# Power_Supply.net
KiCad netlist of a schematic drawn in Altium Designer
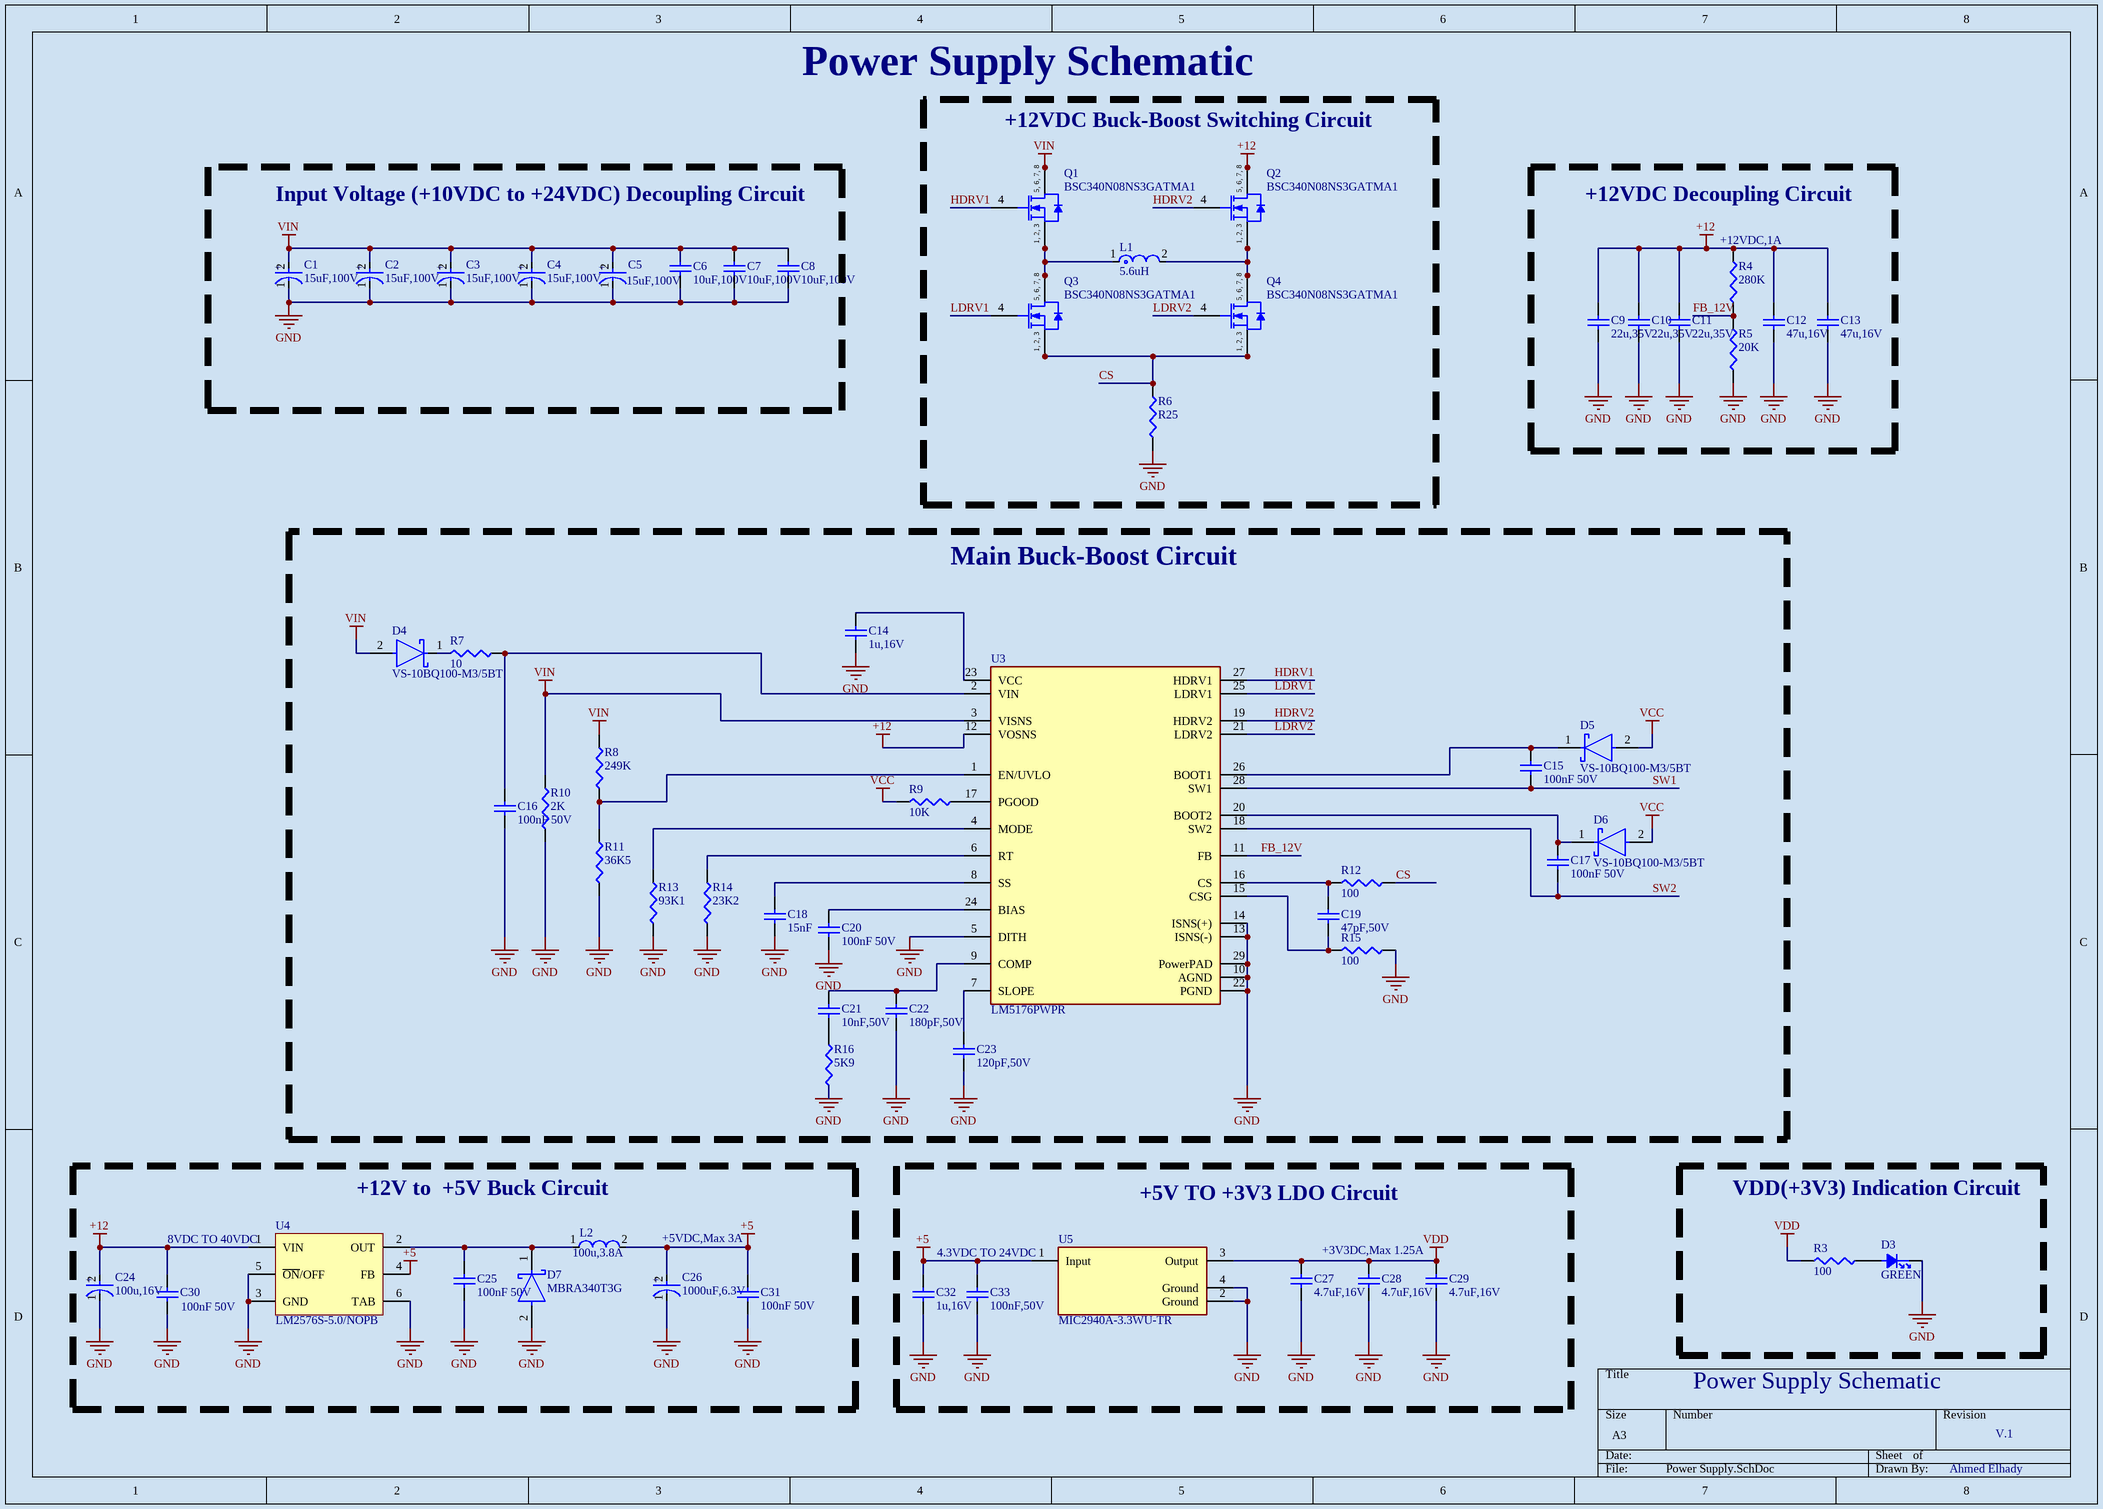
[diagram p0: Power Supply.SchDoc]

(export (version "E")
  (design (tool "Eeschema 10.0.6"))
  (components
    (comp (ref "C1")
      (value "15uF,100V")
      (footprint "FP-SMT-CAP-15U-100V-ELECTROLTIC")
      (description "15 µF 100 V Aluminum - Polymer Capacitors Radial, Can - SMD 40mOhm 1000 Hrs @ 125°C")
      (fields (field (name "MANUFACTURER") "Panasonic") (field (name "MANUFACTURER PART NUMBER") "100SXV15M"))
      (libsource (lib "Sch for NFC") (part "100SXV15M"))
    )
    (comp (ref "C2")
      (value "15uF,100V")
      (footprint "FP-SMT-CAP-15U-100V-ELECTROLTIC")
      (description "15 µF 100 V Aluminum - Polymer Capacitors Radial, Can - SMD 40mOhm 1000 Hrs @ 125°C")
      (fields (field (name "MANUFACTURER") "Panasonic") (field (name "MANUFACTURER PART NUMBER") "100SXV15M"))
      (libsource (lib "Sch for NFC") (part "100SXV15M"))
    )
    (comp (ref "C3")
      (value "15uF,100V")
      (footprint "FP-SMT-CAP-15U-100V-ELECTROLTIC")
      (description "15 µF 100 V Aluminum - Polymer Capacitors Radial, Can - SMD 40mOhm 1000 Hrs @ 125°C")
      (fields (field (name "MANUFACTURER") "Panasonic") (field (name "MANUFACTURER PART NUMBER") "100SXV15M"))
      (libsource (lib "Sch for NFC") (part "100SXV15M"))
    )
    (comp (ref "C4")
      (value "15uF,100V")
      (footprint "FP-SMT-CAP-15U-100V-ELECTROLTIC")
      (description "15 µF 100 V Aluminum - Polymer Capacitors Radial, Can - SMD 40mOhm 1000 Hrs @ 125°C")
      (fields (field (name "MANUFACTURER") "Panasonic") (field (name "MANUFACTURER PART NUMBER") "100SXV15M"))
      (libsource (lib "Sch for NFC") (part "100SXV15M"))
    )
    (comp (ref "C5")
      (value "15uF,100V")
      (footprint "FP-SMT-CAP-15U-100V-ELECTROLTIC")
      (description "15 µF 100 V Aluminum - Polymer Capacitors Radial, Can - SMD 40mOhm 1000 Hrs @ 125°C")
      (fields (field (name "MANUFACTURER") "Panasonic") (field (name "MANUFACTURER PART NUMBER") "100SXV15M"))
      (libsource (lib "Sch for NFC") (part "100SXV15M"))
    )
    (comp (ref "C6")
      (value "10uF,100V")
      (footprint "CAP-1210-10U-100V")
      (description "10 µF ±10% 100V Ceramic Capacitor X7R 1210 (3225 Metric)")
      (fields
        (field (name "MANUFACTURER") "TDK")
        (field (name "MANUFACTURER PART NUMBER") "C3225X7R2A106K250AC")
      )
      (libsource (lib "Sch for NFC") (part "C3225X7R2A106K250AC"))
    )
    (comp (ref "C7")
      (value "10uF,100V")
      (footprint "CAP-1210-10U-100V")
      (description "10 µF ±10% 100V Ceramic Capacitor X7R 1210 (3225 Metric)")
      (fields
        (field (name "MANUFACTURER") "TDK")
        (field (name "MANUFACTURER PART NUMBER") "C3225X7R2A106K250AC")
      )
      (libsource (lib "Sch for NFC") (part "C3225X7R2A106K250AC"))
    )
    (comp (ref "C8")
      (value "10uF,100V")
      (footprint "CAP-1210-10U-100V")
      (description "10 µF ±10% 100V Ceramic Capacitor X7R 1210 (3225 Metric)")
      (fields
        (field (name "MANUFACTURER") "TDK")
        (field (name "MANUFACTURER PART NUMBER") "C3225X7R2A106K250AC")
      )
      (libsource (lib "Sch for NFC") (part "C3225X7R2A106K250AC"))
    )
    (comp (ref "C9")
      (value "22u,35V")
      (footprint "TDK_0805-22uF-35V")
      (description "22 µF ±20% 35V Ceramic Capacitor X5R 0805 (2012 Metric)")
      (fields
        (field (name "MANUFACTURER") "TDK")
        (field (name "MANUFACTURER PART NUMBER") "C2012X5R1V226M125AC")
      )
      (libsource (lib "Sch for NFC") (part "C2012X5R1V226M125AC"))
    )
    (comp (ref "C10")
      (value "22u,35V")
      (footprint "TDK_0805-22uF-35V")
      (description "22 µF ±20% 35V Ceramic Capacitor X5R 0805 (2012 Metric)")
      (fields
        (field (name "MANUFACTURER") "TDK")
        (field (name "MANUFACTURER PART NUMBER") "C2012X5R1V226M125AC")
      )
      (libsource (lib "Sch for NFC") (part "C2012X5R1V226M125AC"))
    )
    (comp (ref "C11")
      (value "22u,35V")
      (footprint "TDK_0805-22uF-35V")
      (description "22 µF ±20% 35V Ceramic Capacitor X5R 0805 (2012 Metric)")
      (fields
        (field (name "MANUFACTURER") "TDK")
        (field (name "MANUFACTURER PART NUMBER") "C2012X5R1V226M125AC")
      )
      (libsource (lib "Sch for NFC") (part "C2012X5R1V226M125AC"))
    )
    (comp (ref "C12")
      (value "47u,16V")
      (footprint "cap1210-47u-16v")
      (description "47 µF ±10% 16V Ceramic Capacitor X5R 1210 (3225 Metric)")
      (fields
        (field (name "MANUFACTURER") "Murata")
        (field (name "MANUFACTURER PART NUMBER") "GRM32ER61C476KE15L")
      )
      (libsource (lib "Sch for NFC") (part "GRM32ER61C476KE15L"))
    )
    (comp (ref "C13")
      (value "47u,16V")
      (footprint "cap1210-47u-16v")
      (description "47 µF ±10% 16V Ceramic Capacitor X5R 1210 (3225 Metric)")
      (fields
        (field (name "MANUFACTURER") "Murata")
        (field (name "MANUFACTURER PART NUMBER") "GRM32ER61C476KE15L")
      )
      (libsource (lib "Sch for NFC") (part "GRM32ER61C476KE15L"))
    )
    (comp (ref "C14")
      (value "1u,16V")
      (footprint "0603 (1608 Metric)-CAP-100NF-50V")
      (description "1 µF ±10% 16V Ceramic Capacitor X7R 0603 (1608 Metric)")
      (fields
        (field (name "MANUFACTURER") "Taiyo Yuden")
        (field (name "MANUFACTURER PART NUMBER") "EMK107B7105KA-T")
      )
      (libsource (lib "Sch for NFC") (part "EMK107B7105KA-T"))
    )
    (comp (ref "C15")
      (value "100nF 50V")
      (footprint "0603 (1608 Metric)-CAP-100NF-50V")
      (description "0.1 µF ±10% 50V Ceramic Capacitor X7R 0603 (1608 Metric)")
      (fields
        (field (name "MANUFACTURER") "TDK")
        (field (name "MANUFACTURER PART NUMBER") "CGA3E2X7R1H104K080AA")
      )
      (libsource (lib "Sch for NFC") (part "CGA3E2X7R1H104K080AA"))
    )
    (comp (ref "C16")
      (value "100nF 50V")
      (footprint "0603 (1608 Metric)-CAP-100NF-50V")
      (description "0.1 µF ±10% 50V Ceramic Capacitor X7R 0603 (1608 Metric)")
      (fields
        (field (name "MANUFACTURER") "TDK")
        (field (name "MANUFACTURER PART NUMBER") "CGA3E2X7R1H104K080AA")
      )
      (libsource (lib "Sch for NFC") (part "CGA3E2X7R1H104K080AA"))
    )
    (comp (ref "C17")
      (value "100nF 50V")
      (footprint "0603 (1608 Metric)-CAP-100NF-50V")
      (description "0.1 µF ±10% 50V Ceramic Capacitor X7R 0603 (1608 Metric)")
      (fields
        (field (name "MANUFACTURER") "TDK")
        (field (name "MANUFACTURER PART NUMBER") "CGA3E2X7R1H104K080AA")
      )
      (libsource (lib "Sch for NFC") (part "CGA3E2X7R1H104K080AA"))
    )
    (comp (ref "C18")
      (value "15nF")
      (footprint "0603-Cap-15nf-25v")
      (description "15nF ±5% 25V Ceramic Capacitor C0G, NP0 0603 (1608 Metric)")
      (fields
        (field (name "MANUFACTURER") "KEMET")
        (field (name "MANUFACTURER PART NUMBER") "C0603C153J3GACTU")
      )
      (libsource (lib "Sch for NFC") (part "C0603C153J3GACTU"))
    )
    (comp (ref "C19")
      (value "47pF,50V")
      (footprint "CAP-0603-47PF-50V")
      (description "47 pF ±5% 50V Ceramic Capacitor C0G, NP0 0603 (1608 Metric)")
      (fields
        (field (name "MANUFACTURER") "KYOCERA AVX")
        (field (name "MANUFACTURER PART NUMBER") "KGM15ACG1H470JT")
      )
      (libsource (lib "Sch for NFC") (part "KGM15ACG1H470JT"))
    )
    (comp (ref "C20")
      (value "100nF 50V")
      (footprint "0603 (1608 Metric)-CAP-100NF-50V")
      (description "0.1 µF ±10% 50V Ceramic Capacitor X7R 0603 (1608 Metric)")
      (fields
        (field (name "MANUFACTURER") "TDK")
        (field (name "MANUFACTURER PART NUMBER") "CGA3E2X7R1H104K080AA")
      )
      (libsource (lib "Sch for NFC") (part "CGA3E2X7R1H104K080AA"))
    )
    (comp (ref "C21")
      (value "10nF,50V")
      (footprint "CAPC1005X90N")
      (description "10000 pF ±10% 50V Ceramic Capacitor X7R 0402 (1005 Metric)")
      (fields
        (field (name "MANUFACTURER") "TDK")
        (field (name "MANUFACTURER PART NUMBER") "CGA2B3X7R1H103K050BE")
      )
      (libsource (lib "Sch for NFC") (part "CGA2B3X7R1H103K050BE"))
    )
    (comp (ref "C22")
      (value "180pF,50V")
      (footprint "C0805C-180pF-50V")
      (description "180 pF ±10% 50V Ceramic Capacitor C0G, NP0 0805 (2012 Metric)")
      (fields
        (field (name "MANUFACTURER") "KEMET")
        (field (name "MANUFACTURER PART NUMBER") "C0805C181K5GACTU")
      )
      (libsource (lib "Sch for NFC") (part "C0805C181K5GACTU"))
    )
    (comp (ref "C23")
      (value "120pF,50V")
      (footprint "FP-0603-120PF-50V")
      (description "120 pF ±5% 50V Ceramic Capacitor C0G, NP0 0603 (1608 Metric)")
      (fields
        (field (name "MANUFACTURER") "Samsung Electro-Mechanics")
        (field (name "MANUFACTURER PART NUMBER") "CL10C121JB8NNNC")
      )
      (libsource (lib "Sch for NFC") (part "CL10C121JB8NNNC"))
    )
    (comp (ref "C24")
      (value "100u,16V")
      (footprint "CAP_EEEFP1C101AV")
      (description "100 µF 16 V Aluminum Electrolytic Capacitors Radial, Can - SMD 260mOhm @ 100kHz 2000 Hrs @ 105°C")
      (fields
        (field (name "MANUFACTURER") "Panasonic")
        (field (name "MANUFACTURER PART NUMBER") "EEEFP1C101AV")
      )
      (libsource (lib "Sch for NFC") (part "EEEFP1C101AV"))
    )
    (comp (ref "C25")
      (value "100nF 50V")
      (footprint "0603 (1608 Metric)-CAP-100NF-50V")
      (description "0.1 µF ±10% 50V Ceramic Capacitor X7R 0603 (1608 Metric)")
      (fields
        (field (name "MANUFACTURER") "TDK")
        (field (name "MANUFACTURER PART NUMBER") "CGA3E2X7R1H104K080AA")
      )
      (libsource (lib "Sch for NFC") (part "CGA3E2X7R1H104K080AA"))
    )
    (comp (ref "C26")
      (value "1000uF,6.3V")
      (footprint "CAP_1000uF-SMT")
      (description "1000 µF 6.3 V Aluminum Electrolytic Capacitors Radial, Can - SMD 80mOhm @ 100kHz 2000 Hrs @ 105°C")
      (fields
        (field (name "MANUFACTURER") "Panasonic")
        (field (name "MANUFACTURER PART NUMBER") "EEE-FP0J102AL")
      )
      (libsource (lib "Sch for NFC") (part "EEE-FP0J102AL"))
    )
    (comp (ref "C27")
      (value "4.7uF,16V")
      (footprint "CAPC1005X90N")
      (description "4.7 µF ±20% 16V Ceramic Capacitor X5R 0402 (1005 Metric)")
      (fields
        (field (name "MANUFACTURER") "Samsung Electro-Mechanics")
        (field (name "MANUFACTURER PART NUMBER") "CL05A475MO5NUNC")
      )
      (libsource (lib "Sch for NFC") (part "CL05A475MO5NUNC"))
    )
    (comp (ref "C28")
      (value "4.7uF,16V")
      (footprint "CAPC1005X90N")
      (description "4.7 µF ±20% 16V Ceramic Capacitor X5R 0402 (1005 Metric)")
      (fields
        (field (name "MANUFACTURER") "Samsung Electro-Mechanics")
        (field (name "MANUFACTURER PART NUMBER") "CL05A475MO5NUNC")
      )
      (libsource (lib "Sch for NFC") (part "CL05A475MO5NUNC"))
    )
    (comp (ref "C29")
      (value "4.7uF,16V")
      (footprint "CAPC1005X90N")
      (description "4.7 µF ±20% 16V Ceramic Capacitor X5R 0402 (1005 Metric)")
      (fields
        (field (name "MANUFACTURER") "Samsung Electro-Mechanics")
        (field (name "MANUFACTURER PART NUMBER") "CL05A475MO5NUNC")
      )
      (libsource (lib "Sch for NFC") (part "CL05A475MO5NUNC"))
    )
    (comp (ref "C30")
      (value "100nF 50V")
      (footprint "0603 (1608 Metric)-CAP-100NF-50V")
      (description "0.1 µF ±10% 50V Ceramic Capacitor X7R 0603 (1608 Metric)")
      (fields
        (field (name "MANUFACTURER") "TDK")
        (field (name "MANUFACTURER PART NUMBER") "CGA3E2X7R1H104K080AA")
      )
      (libsource (lib "Sch for NFC") (part "CGA3E2X7R1H104K080AA"))
    )
    (comp (ref "C31")
      (value "100nF 50V")
      (footprint "0603 (1608 Metric)-CAP-100NF-50V")
      (description "0.1 µF ±10% 50V Ceramic Capacitor X7R 0603 (1608 Metric)")
      (fields
        (field (name "MANUFACTURER") "TDK")
        (field (name "MANUFACTURER PART NUMBER") "CGA3E2X7R1H104K080AA")
      )
      (libsource (lib "Sch for NFC") (part "CGA3E2X7R1H104K080AA"))
    )
    (comp (ref "C32")
      (value "1u,16V")
      (footprint "0603 (1608 Metric)-CAP-100NF-50V")
      (description "1 µF ±10% 16V Ceramic Capacitor X7R 0603 (1608 Metric)")
      (fields
        (field (name "MANUFACTURER") "Taiyo Yuden")
        (field (name "MANUFACTURER PART NUMBER") "EMK107B7105KA-T")
      )
      (libsource (lib "Sch for NFC") (part "EMK107B7105KA-T"))
    )
    (comp (ref "C33")
      (value "100nF,50V")
      (footprint "0603 (1608 Metric)-CAP-100NF-50V")
      (description "0.1 µF ±10% 50V Ceramic Capacitor X7R 0603 (1608 Metric)")
      (fields
        (field (name "MANUFACTURER") "TDK")
        (field (name "MANUFACTURER PART NUMBER") "CGA3E2X7R1H104K080AA")
      )
      (libsource (lib "Sch for NFC") (part "CGA3E2X7R1H104K080AA"))
    )
    (comp (ref "D3")
      (value "GREEN")
      (footprint "LED0402G")
      (description "Yellow-Green 571nm LED Indication - Discrete 2V 0402 (1005 Metric)")
      (fields
        (field (name "MANUFACTURER") "Vishay")
        (field (name "MANUFACTURER PART NUMBER") "VLMG1500-GS08")
      )
      (libsource (lib "Sch for NFC") (part "VLMG1500-GS08"))
    )
    (comp (ref "D4")
      (value "VS-10BQ100-M3/5BT")
      (footprint "Diode Schottky 100V 1A 2-Pin SMB T/R / DIODE SCHOTTK")
      (description "Rectifier Diode Schottky 100V 1A 2-Pin SMB T/R / DIODE SCHOTTKY 100V 1A SMB")
      (fields (field (name "MANUFACTURER") "Vishay"))
      (libsource (lib "Sch for NFC") (part "VS-10BQ100-M3/5BT"))
    )
    (comp (ref "D5")
      (value "VS-10BQ100-M3/5BT")
      (footprint "Diode Schottky 100V 1A 2-Pin SMB T/R / DIODE SCHOTTK")
      (description "Rectifier Diode Schottky 100V 1A 2-Pin SMB T/R / DIODE SCHOTTKY 100V 1A SMB")
      (fields (field (name "MANUFACTURER") "Vishay"))
      (libsource (lib "Sch for NFC") (part "VS-10BQ100-M3/5BT"))
    )
    (comp (ref "D6")
      (value "VS-10BQ100-M3/5BT")
      (footprint "Diode Schottky 100V 1A 2-Pin SMB T/R / DIODE SCHOTTK")
      (description "Rectifier Diode Schottky 100V 1A 2-Pin SMB T/R / DIODE SCHOTTKY 100V 1A SMB")
      (fields (field (name "MANUFACTURER") "Vishay"))
      (libsource (lib "Sch for NFC") (part "VS-10BQ100-M3/5BT"))
    )
    (comp (ref "D7")
      (value "MBRA340T3G")
      (footprint "Diode-SMD-Schotty-40V-3A")
      (description "Diode; Schottky Barrier; Vr 40V; If 3A; Pkg SMA; Vf 0.45V; Tj +150degc; Cs 100A; Ir 15mA")
      (fields (field (name "MANUFACTURER") "onsemi"))
      (libsource (lib "Sch for NFC") (part "MBRA340T3G"))
    )
    (comp (ref "L1")
      (value "5.6uH")
      (footprint "Coilcraft_XAL5050_MFG")
      (description "5.6 µH Shielded Molded Inductor 7.2 A 25.8mOhm Max Nonstandard")
      (fields
        (field (name "MANUFACTURER") "Coilcraft")
        (field (name "MANUFACTURER PART NUMBER") "XAL5050-562MEC")
      )
      (libsource (lib "Sch for NFC") (part "XAL5050-562MEC"))
    )
    (comp (ref "L2")
      (value "100u,3.8A")
      (footprint "COIL-SMD-100U-3.8A")
      (description "100 µH Shielded Molded Inductor 3.8 A 161mOhm Max Nonstandard")
      (fields
        (field (name "MANUFACTURER") "Abracon")
        (field (name "MANUFACTURER PART NUMBER") "AMDLA1306Q-101MT")
      )
      (libsource (lib "Sch for NFC") (part "AMDLA1306Q-101MT"))
    )
    (comp (ref "Q1")
      (value "BSC340N08NS3GATMA1")
      (footprint "TDSON-8-MOSFET-N-CHANNEL")
      (description "N-Channel 80 V 7A (Ta), 23A (Tc) 2.5W (Ta), 32W (Tc) Surface Mount PG-TDSON-8-5")
      (fields (field (name "MANUFACTURER") "Infineon"))
      (libsource (lib "Sch for NFC") (part "BSC340N08NS3GATMA1"))
    )
    (comp (ref "Q2")
      (value "BSC340N08NS3GATMA1")
      (footprint "TDSON-8-MOSFET-N-CHANNEL")
      (description "N-Channel 80 V 7A (Ta), 23A (Tc) 2.5W (Ta), 32W (Tc) Surface Mount PG-TDSON-8-5")
      (fields (field (name "MANUFACTURER") "Infineon"))
      (libsource (lib "Sch for NFC") (part "BSC340N08NS3GATMA1"))
    )
    (comp (ref "Q3")
      (value "BSC340N08NS3GATMA1")
      (footprint "TDSON-8-MOSFET-N-CHANNEL")
      (description "N-Channel 80 V 7A (Ta), 23A (Tc) 2.5W (Ta), 32W (Tc) Surface Mount PG-TDSON-8-5")
      (fields (field (name "MANUFACTURER") "Infineon"))
      (libsource (lib "Sch for NFC") (part "BSC340N08NS3GATMA1"))
    )
    (comp (ref "Q4")
      (value "BSC340N08NS3GATMA1")
      (footprint "TDSON-8-MOSFET-N-CHANNEL")
      (description "N-Channel 80 V 7A (Ta), 23A (Tc) 2.5W (Ta), 32W (Tc) Surface Mount PG-TDSON-8-5")
      (fields (field (name "MANUFACTURER") "Infineon"))
      (libsource (lib "Sch for NFC") (part "BSC340N08NS3GATMA1"))
    )
    (comp (ref "R3")
      (value "100")
      (footprint "0603-RES-10OHM-0.1W")
      (description "100 Ohms ±1% 0.125W, 1/8W Chip Resistor 0603 (1608 Metric) Automotive AEC-Q200 Thick Film")
      (fields
        (field (name "MANUFACTURER") "Vishay")
        (field (name "MANUFACTURER PART NUMBER") "CRCW0603100RFKEA")
      )
      (libsource (lib "Sch for NFC") (part "CRCW0603100RFKEA"))
    )
    (comp (ref "R4")
      (value "280K")
      (footprint "Vishay_CRCW0603-280k")
      (description "280 kOhms ±1% 0.125W, 1/8W Chip Resistor 0603 (1608 Metric) Automotive AEC-Q200 Thick Film")
      (fields
        (field (name "MANUFACTURER") "Vishay")
        (field (name "MANUFACTURER PART NUMBER") "CRCW0603280KFKEA")
      )
      (libsource (lib "Sch for NFC") (part "CRCW0603280KFKEA"))
    )
    (comp (ref "R5")
      (value "20K")
      (footprint "20K-0603-Yageo_-_Phycomp_RC0603_0")
      (description "20 kOhms ±1% 0.1W, 1/10W Chip Resistor 0603 (1608 Metric) Moisture Resistant Thick Film")
      (fields
        (field (name "MANUFACTURER") "Yageo Group")
        (field (name "MANUFACTURER PART NUMBER") "RC0603FR-0720KL")
      )
      (libsource (lib "Sch for NFC") (part "RC0603FR-0720KL"))
    )
    (comp (ref "R6")
      (value "R25")
      (footprint "RESC3015X65N-25mohm")
      (description "25 mOhms ±1% 0.5W, 1/2W Chip Resistor 1206 (3216 Metric) Current Sense Thick Film")
      (fields
        (field (name "MANUFACTURER") "Stackpole Electronics")
        (field (name "MANUFACTURER PART NUMBER") "CSR1206FK25L0")
      )
      (libsource (lib "Sch for NFC") (part "CSR1206FK25L0"))
    )
    (comp (ref "R7")
      (value "10")
      (footprint "0603-RES-10OHM-0.1W")
      (description "10 Ohms ±1% 0.1W, 1/10W Chip Resistor 0603 (1608 Metric) Moisture Resistant Thick Film")
      (fields
        (field (name "MANUFACTURER") "Vishay")
        (field (name "MANUFACTURER PART NUMBER") "CRCW060310R0FKEA")
      )
      (libsource (lib "Sch for NFC") (part "CRCW060310R0FKEA"))
    )
    (comp (ref "R8")
      (value "249K")
      (footprint "RESC1005X37N")
      (description "249 kOhms ±1% 0.063W, 1/16W Chip Resistor 0402 (1005 Metric) Automotive AEC-Q200 Thick Film")
      (fields
        (field (name "MANUFACTURER") "Vishay")
        (field (name "MANUFACTURER PART NUMBER") "CRCW0402249KFKED")
      )
      (libsource (lib "Sch for NFC") (part "CRCW0402249KFKED"))
    )
    (comp (ref "R9")
      (value "10K")
      (footprint "YAGEO-0603-10K-0.1W")
      (description "10 kOhms ±1% 0.1W, 1/10W Chip Resistor 0603 (1608 Metric) Moisture Resistant Thick Film")
      (fields
        (field (name "MANUFACTURER") "Yageo Group")
        (field (name "MANUFACTURER PART NUMBER") "RC0603FR-0710KL")
      )
      (libsource (lib "Sch for NFC") (part "RC0603FR-0710KL"))
    )
    (comp (ref "R10")
      (value "2K")
      (footprint "2K_0.125W_RESC2013X70X40NL20T20")
      (description "2 kOhms ±1% 0.125W, 1/8W Chip Resistor 0805 (2012 Metric) Automotive AEC-Q200 Thick Film")
      (fields
        (field (name "MANUFACTURER") "Panasonic")
        (field (name "MANUFACTURER PART NUMBER") "ERJ-6ENF2001V")
      )
      (libsource (lib "Sch for NFC") (part "ERJ-6ENF2001V"))
    )
    (comp (ref "R11")
      (value "36K5")
      (footprint "RESC1005X37N")
      (fields
        (field (name "MANUFACTURER") "Yageo Group")
        (field (name "MANUFACTURER PART NUMBER") "AC0402FR-0736K5L")
        (field (name "TOLERANCE") "1%")
      )
      (libsource (lib "Sch for NFC") (part "AC0402FR-0736K5L"))
    )
    (comp (ref "R12")
      (value "100")
      (footprint "0603-RES-10OHM-0.1W")
      (description "100 Ohms ±1% 0.125W, 1/8W Chip Resistor 0603 (1608 Metric) Automotive AEC-Q200 Thick Film")
      (fields
        (field (name "MANUFACTURER") "Vishay")
        (field (name "MANUFACTURER PART NUMBER") "CRCW0603100RFKEA")
      )
      (libsource (lib "Sch for NFC") (part "CRCW0603100RFKEA"))
    )
    (comp (ref "R13")
      (value "93K1")
      (footprint "RC0603_MFG-93.1k")
      (description "93.1 kOhms ±1% 0.1W, 1/10W Chip Resistor 0603 (1608 Metric) Moisture Resistant Thick Film")
      (fields
        (field (name "MANUFACTURER") "Yageo Group")
        (field (name "MANUFACTURER PART NUMBER") "RC0603FR-0793K1L")
      )
      (libsource (lib "Sch for NFC") (part "RC0603FR-0793K1L"))
    )
    (comp (ref "R14")
      (value "23K2")
      (footprint "RESC1005X37N")
      (description "23.2 kOhms ±1% 0.063W, 1/16W Chip Resistor 0402 (1005 Metric) Automotive AEC-Q200 Thick Film")
      (fields
        (field (name "MANUFACTURER") "Vishay")
        (field (name "MANUFACTURER PART NUMBER") "CRCW040223K2FKED")
      )
      (libsource (lib "Sch for NFC") (part "CRCW040223K2FKED"))
    )
    (comp (ref "R15")
      (value "100")
      (footprint "0603-RES-10OHM-0.1W")
      (description "100 Ohms ±1% 0.125W, 1/8W Chip Resistor 0603 (1608 Metric) Automotive AEC-Q200 Thick Film")
      (fields
        (field (name "MANUFACTURER") "Vishay")
        (field (name "MANUFACTURER PART NUMBER") "CRCW0603100RFKEA")
      )
      (libsource (lib "Sch for NFC") (part "CRCW0603100RFKEA"))
    )
    (comp (ref "R16")
      (value "5K9")
      (footprint "RESC1005X37N")
      (description "5.9 kOhms ±1% 0.063W, 1/16W Chip Resistor 0402 (1005 Metric) Automotive AEC-Q200 Thick Film")
      (fields
        (field (name "MANUFACTURER") "Vishay")
        (field (name "MANUFACTURER PART NUMBER") "CRCW04025K90FKED")
      )
      (libsource (lib "Sch for NFC") (part "CRCW04025K90FKED"))
    )
    (comp (ref "U3")
      (value "LM5176PWPR")
      (footprint "FP-TSSOP28-BUCK-BOOST-LM5176PWPR")
      (description "Buck-Boost Regulator Positive Output Step-Up/Step-Down DC-DC Controller IC 28-HTSSOP")
      (fields (field (name "MANUFACTURER") "Texas Instruments"))
      (libsource (lib "Sch for NFC") (part "LM5176PWPR"))
    )
    (comp (ref "U4")
      (value "LM2576S-5.0/NOPB")
      (footprint "DPAK-LM2576S-5.0/NOPB")
      (fields (field (name "MANUFACTURER") "Texas Instruments"))
      (libsource (lib "Sch for NFC") (part "LM2576S-5.0/NOPB"))
    )
    (comp (ref "U5")
      (value "MIC2940A-3.3WU-TR")
      (footprint "FP-TO263-3LD-REG-BUCK-3.3V")
      (description "Linear Voltage Regulator IC Positive Fixed 1 Output 1.25A TO-263-3")
      (fields (field (name "MANUFACTURER") "Microchip"))
      (libsource (lib "Sch for NFC") (part "MIC2940A-3.3WU-TR"))
    )
  )
  (nets
    (net (code "1") (name "+5") (class "Default")
      (node (ref "C26") (pin "2") (pinfunction "ANODE_2") (pintype "passive"))
      (node (ref "C31") (pin "2") (pinfunction "2_2") (pintype "passive"))
      (node (ref "C32") (pin "1") (pinfunction "1_1") (pintype "passive"))
      (node (ref "C33") (pin "2") (pinfunction "2_2") (pintype "passive"))
      (node (ref "L2") (pin "2") (pinfunction "2_2") (pintype "passive"))
      (node (ref "U4") (pin "4") (pinfunction "FB_4") (pintype "passive"))
      (node (ref "U5") (pin "1") (pinfunction "Input_1") (pintype "power_in"))
    )
    (net (code "2") (name "+12") (class "Default")
      (node (ref "C10") (pin "2") (pinfunction "2_2") (pintype "passive"))
      (node (ref "C11") (pin "2") (pinfunction "2_2") (pintype "passive"))
      (node (ref "C12") (pin "2") (pinfunction "2_2") (pintype "passive"))
      (node (ref "C13") (pin "2") (pinfunction "2_2") (pintype "passive"))
      (node (ref "C24") (pin "2") (pinfunction "ANODE_2") (pintype "passive"))
      (node (ref "C30") (pin "2") (pinfunction "2_2") (pintype "passive"))
      (node (ref "C9") (pin "2") (pinfunction "2_2") (pintype "passive"))
      (node (ref "Q2") (pin "5") (pinfunction "DRAIN_5") (pintype "passive"))
      (node (ref "Q2") (pin "6") (pinfunction "DRAIN_6") (pintype "passive"))
      (node (ref "Q2") (pin "7") (pinfunction "DRAIN_7") (pintype "passive"))
      (node (ref "Q2") (pin "8") (pinfunction "DRAIN_8") (pintype "passive"))
      (node (ref "R4") (pin "2") (pinfunction "2_2") (pintype "passive"))
      (node (ref "U3") (pin "12") (pinfunction "VOSNS_12") (pintype "passive"))
      (node (ref "U4") (pin "1") (pinfunction "VIN_1") (pintype "passive"))
    )
    (net (code "3") (name "/CS") (class "Default")
      (node (ref "Q3") (pin "1") (pinfunction "SOURCE_1") (pintype "passive"))
      (node (ref "Q3") (pin "2") (pinfunction "SOURCE_2") (pintype "passive"))
      (node (ref "Q3") (pin "3") (pinfunction "SOURCE_3") (pintype "passive"))
      (node (ref "Q4") (pin "1") (pinfunction "SOURCE_1") (pintype "passive"))
      (node (ref "Q4") (pin "2") (pinfunction "SOURCE_2") (pintype "passive"))
      (node (ref "Q4") (pin "3") (pinfunction "SOURCE_3") (pintype "passive"))
      (node (ref "R12") (pin "1") (pinfunction "1_1") (pintype "passive"))
      (node (ref "R6") (pin "2") (pinfunction "2_2") (pintype "passive"))
    )
    (net (code "4") (name "/FB_12V") (class "Default")
      (node (ref "R4") (pin "1") (pinfunction "1_1") (pintype "passive"))
      (node (ref "R5") (pin "2") (pinfunction "2_2") (pintype "passive"))
      (node (ref "U3") (pin "11") (pinfunction "FB_11") (pintype "passive"))
    )
    (net (code "5") (name "/HDRV1") (class "Default")
      (node (ref "Q1") (pin "4") (pinfunction "GATE_4") (pintype "passive"))
      (node (ref "U3") (pin "27") (pinfunction "HDRV1_27") (pintype "passive"))
    )
    (net (code "6") (name "/HDRV2") (class "Default")
      (node (ref "Q2") (pin "4") (pinfunction "GATE_4") (pintype "passive"))
      (node (ref "U3") (pin "19") (pinfunction "HDRV2_19") (pintype "passive"))
    )
    (net (code "7") (name "/LDRV1") (class "Default")
      (node (ref "Q3") (pin "4") (pinfunction "GATE_4") (pintype "passive"))
      (node (ref "U3") (pin "25") (pinfunction "LDRV1_25") (pintype "passive"))
    )
    (net (code "8") (name "/LDRV2") (class "Default")
      (node (ref "Q4") (pin "4") (pinfunction "GATE_4") (pintype "passive"))
      (node (ref "U3") (pin "21") (pinfunction "LDRV2_21") (pintype "passive"))
    )
    (net (code "9") (name "/SW1") (class "Default")
      (node (ref "C15") (pin "1") (pinfunction "1_1") (pintype "passive"))
      (node (ref "U3") (pin "28") (pinfunction "SW1_28") (pintype "passive"))
    )
    (net (code "10") (name "/SW2") (class "Default")
      (node (ref "C17") (pin "1") (pinfunction "1_1") (pintype "passive"))
      (node (ref "U3") (pin "18") (pinfunction "SW2_18") (pintype "passive"))
    )
    (net (code "11") (name "GND") (class "Default")
      (node (ref "C1") (pin "1") (pinfunction "C_1") (pintype "passive"))
      (node (ref "C10") (pin "1") (pinfunction "1_1") (pintype "passive"))
      (node (ref "C11") (pin "1") (pinfunction "1_1") (pintype "passive"))
      (node (ref "C12") (pin "1") (pinfunction "1_1") (pintype "passive"))
      (node (ref "C13") (pin "1") (pinfunction "1_1") (pintype "passive"))
      (node (ref "C14") (pin "1") (pinfunction "1_1") (pintype "passive"))
      (node (ref "C16") (pin "1") (pinfunction "1_1") (pintype "passive"))
      (node (ref "C18") (pin "1") (pinfunction "1_1") (pintype "passive"))
      (node (ref "C2") (pin "1") (pinfunction "C_1") (pintype "passive"))
      (node (ref "C20") (pin "1") (pinfunction "1_1") (pintype "passive"))
      (node (ref "C22") (pin "1") (pinfunction "1_1") (pintype "passive"))
      (node (ref "C23") (pin "1") (pinfunction "1_1") (pintype "passive"))
      (node (ref "C24") (pin "1") (pinfunction "CATHODE_1") (pintype "passive"))
      (node (ref "C25") (pin "1") (pinfunction "1_1") (pintype "passive"))
      (node (ref "C26") (pin "1") (pinfunction "CATHODE_1") (pintype "passive"))
      (node (ref "C27") (pin "1") (pinfunction "1_1") (pintype "passive"))
      (node (ref "C28") (pin "1") (pinfunction "1_1") (pintype "passive"))
      (node (ref "C29") (pin "1") (pinfunction "1_1") (pintype "passive"))
      (node (ref "C3") (pin "1") (pinfunction "C_1") (pintype "passive"))
      (node (ref "C30") (pin "1") (pinfunction "1_1") (pintype "passive"))
      (node (ref "C31") (pin "1") (pinfunction "1_1") (pintype "passive"))
      (node (ref "C32") (pin "2") (pinfunction "2_2") (pintype "passive"))
      (node (ref "C33") (pin "1") (pinfunction "1_1") (pintype "passive"))
      (node (ref "C4") (pin "1") (pinfunction "C_1") (pintype "passive"))
      (node (ref "C5") (pin "1") (pinfunction "C_1") (pintype "passive"))
      (node (ref "C6") (pin "1") (pinfunction "1_1") (pintype "passive"))
      (node (ref "C7") (pin "1") (pinfunction "1_1") (pintype "passive"))
      (node (ref "C8") (pin "1") (pinfunction "1_1") (pintype "passive"))
      (node (ref "C9") (pin "1") (pinfunction "1_1") (pintype "passive"))
      (node (ref "D3") (pin "1") (pinfunction "Cathode_1") (pintype "passive"))
      (node (ref "D7") (pin "2") (pinfunction "A_2") (pintype "passive"))
      (node (ref "R10") (pin "1") (pinfunction "1_1") (pintype "passive"))
      (node (ref "R11") (pin "1") (pinfunction "1_1") (pintype "passive"))
      (node (ref "R13") (pin "1") (pinfunction "1_1") (pintype "passive"))
      (node (ref "R14") (pin "1") (pinfunction "1_1") (pintype "passive"))
      (node (ref "R15") (pin "2") (pinfunction "2_2") (pintype "passive"))
      (node (ref "R16") (pin "2") (pinfunction "2_2") (pintype "passive"))
      (node (ref "R5") (pin "1") (pinfunction "1_1") (pintype "passive"))
      (node (ref "R6") (pin "1") (pinfunction "1_1") (pintype "passive"))
      (node (ref "U3") (pin "10") (pinfunction "AGND_10") (pintype "passive"))
      (node (ref "U3") (pin "13") (pinfunction "ISNS(-)_13") (pintype "passive"))
      (node (ref "U3") (pin "14") (pinfunction "ISNS(+)_14") (pintype "passive"))
      (node (ref "U3") (pin "22") (pinfunction "PGND_22") (pintype "passive"))
      (node (ref "U3") (pin "29") (pinfunction "PowerPAD_29") (pintype "passive"))
      (node (ref "U3") (pin "5") (pinfunction "DITH_5") (pintype "passive"))
      (node (ref "U4") (pin "3") (pinfunction "GND_3") (pintype "passive"))
      (node (ref "U4") (pin "5") (pinfunction "~{ON}/OFF_5") (pintype "passive"))
      (node (ref "U4") (pin "6") (pinfunction "TAB_6") (pintype "passive"))
      (node (ref "U5") (pin "2") (pinfunction "Ground_2") (pintype "power_in"))
      (node (ref "U5") (pin "4") (pinfunction "Ground_4") (pintype "power_in"))
    )
    (net (code "12") (name "Net-(C21-Pad1)") (class "Default")
      (node (ref "C21") (pin "1") (pinfunction "1_1") (pintype "passive"))
      (node (ref "R16") (pin "1") (pinfunction "1_1") (pintype "passive"))
    )
    (net (code "13") (name "Net-(D3-Anode)") (class "Default")
      (node (ref "D3") (pin "2") (pinfunction "Anode_2") (pintype "passive"))
      (node (ref "R3") (pin "1") (pinfunction "1_1") (pintype "passive"))
    )
    (net (code "14") (name "Net-(D4-C)") (class "Default")
      (node (ref "D4") (pin "1") (pinfunction "C_1") (pintype "passive"))
      (node (ref "R7") (pin "2") (pinfunction "2_2") (pintype "passive"))
    )
    (net (code "15") (name "Net-(D5-C)") (class "Default")
      (node (ref "C15") (pin "2") (pinfunction "2_2") (pintype "passive"))
      (node (ref "D5") (pin "1") (pinfunction "C_1") (pintype "passive"))
      (node (ref "U3") (pin "26") (pinfunction "BOOT1_26") (pintype "passive"))
    )
    (net (code "16") (name "Net-(D6-C)") (class "Default")
      (node (ref "C17") (pin "2") (pinfunction "2_2") (pintype "passive"))
      (node (ref "D6") (pin "1") (pinfunction "C_1") (pintype "passive"))
      (node (ref "U3") (pin "20") (pinfunction "BOOT2_20") (pintype "passive"))
    )
    (net (code "17") (name "Net-(D7-C)") (class "Default")
      (node (ref "C25") (pin "2") (pinfunction "2_2") (pintype "passive"))
      (node (ref "D7") (pin "1") (pinfunction "C_1") (pintype "passive"))
      (node (ref "L2") (pin "1") (pinfunction "1_1") (pintype "passive"))
      (node (ref "U4") (pin "2") (pinfunction "OUT_2") (pintype "passive"))
    )
    (net (code "18") (name "Net-(L1-Pad1)") (class "Default")
      (node (ref "L1") (pin "1") (pinfunction "1_1") (pintype "passive"))
      (node (ref "Q1") (pin "1") (pinfunction "SOURCE_1") (pintype "passive"))
      (node (ref "Q1") (pin "2") (pinfunction "SOURCE_2") (pintype "passive"))
      (node (ref "Q1") (pin "3") (pinfunction "SOURCE_3") (pintype "passive"))
      (node (ref "Q3") (pin "5") (pinfunction "DRAIN_5") (pintype "passive"))
      (node (ref "Q3") (pin "6") (pinfunction "DRAIN_6") (pintype "passive"))
      (node (ref "Q3") (pin "7") (pinfunction "DRAIN_7") (pintype "passive"))
      (node (ref "Q3") (pin "8") (pinfunction "DRAIN_8") (pintype "passive"))
    )
    (net (code "19") (name "Net-(L1-Pad2)") (class "Default")
      (node (ref "L1") (pin "2") (pinfunction "2_2") (pintype "passive"))
      (node (ref "Q2") (pin "1") (pinfunction "SOURCE_1") (pintype "passive"))
      (node (ref "Q2") (pin "2") (pinfunction "SOURCE_2") (pintype "passive"))
      (node (ref "Q2") (pin "3") (pinfunction "SOURCE_3") (pintype "passive"))
      (node (ref "Q4") (pin "5") (pinfunction "DRAIN_5") (pintype "passive"))
      (node (ref "Q4") (pin "6") (pinfunction "DRAIN_6") (pintype "passive"))
      (node (ref "Q4") (pin "7") (pinfunction "DRAIN_7") (pintype "passive"))
      (node (ref "Q4") (pin "8") (pinfunction "DRAIN_8") (pintype "passive"))
    )
    (net (code "20") (name "Net-(U3-BIAS)") (class "Default")
      (node (ref "C20") (pin "2") (pinfunction "2_2") (pintype "passive"))
      (node (ref "U3") (pin "24") (pinfunction "BIAS_24") (pintype "passive"))
    )
    (net (code "21") (name "Net-(U3-COMP)") (class "Default")
      (node (ref "C21") (pin "2") (pinfunction "2_2") (pintype "passive"))
      (node (ref "C22") (pin "2") (pinfunction "2_2") (pintype "passive"))
      (node (ref "U3") (pin "9") (pinfunction "COMP_9") (pintype "passive"))
    )
    (net (code "22") (name "Net-(U3-CS)") (class "Default")
      (node (ref "C19") (pin "1") (pinfunction "1_1") (pintype "passive"))
      (node (ref "R12") (pin "2") (pinfunction "2_2") (pintype "passive"))
      (node (ref "U3") (pin "16") (pinfunction "CS_16") (pintype "passive"))
    )
    (net (code "23") (name "Net-(U3-CSG)") (class "Default")
      (node (ref "C19") (pin "2") (pinfunction "2_2") (pintype "passive"))
      (node (ref "R15") (pin "1") (pinfunction "1_1") (pintype "passive"))
      (node (ref "U3") (pin "15") (pinfunction "CSG_15") (pintype "passive"))
    )
    (net (code "24") (name "Net-(U3-EN{slash}UVLO)") (class "Default")
      (node (ref "R11") (pin "2") (pinfunction "2_2") (pintype "passive"))
      (node (ref "R8") (pin "1") (pinfunction "1_1") (pintype "passive"))
      (node (ref "U3") (pin "1") (pinfunction "EN/UVLO_1") (pintype "passive"))
    )
    (net (code "25") (name "Net-(U3-MODE)") (class "Default")
      (node (ref "R13") (pin "2") (pinfunction "2_2") (pintype "passive"))
      (node (ref "U3") (pin "4") (pinfunction "MODE_4") (pintype "passive"))
    )
    (net (code "26") (name "Net-(U3-PGOOD)") (class "Default")
      (node (ref "R9") (pin "2") (pinfunction "2_2") (pintype "passive"))
      (node (ref "U3") (pin "17") (pinfunction "PGOOD_17") (pintype "passive"))
    )
    (net (code "27") (name "Net-(U3-RT)") (class "Default")
      (node (ref "R14") (pin "2") (pinfunction "2_2") (pintype "passive"))
      (node (ref "U3") (pin "6") (pinfunction "RT_6") (pintype "passive"))
    )
    (net (code "28") (name "Net-(U3-SLOPE)") (class "Default")
      (node (ref "C23") (pin "2") (pinfunction "2_2") (pintype "passive"))
      (node (ref "U3") (pin "7") (pinfunction "SLOPE_7") (pintype "passive"))
    )
    (net (code "29") (name "Net-(U3-SS)") (class "Default")
      (node (ref "C18") (pin "2") (pinfunction "2_2") (pintype "passive"))
      (node (ref "U3") (pin "8") (pinfunction "SS_8") (pintype "passive"))
    )
    (net (code "30") (name "Net-(U3-VCC)") (class "Default")
      (node (ref "C14") (pin "2") (pinfunction "2_2") (pintype "passive"))
      (node (ref "U3") (pin "23") (pinfunction "VCC_23") (pintype "passive"))
    )
    (net (code "31") (name "Net-(U3-VIN)") (class "Default")
      (node (ref "C16") (pin "2") (pinfunction "2_2") (pintype "passive"))
      (node (ref "R7") (pin "1") (pinfunction "1_1") (pintype "passive"))
      (node (ref "U3") (pin "2") (pinfunction "VIN_2") (pintype "passive"))
    )
    (net (code "32") (name "VCC") (class "Default")
      (node (ref "D5") (pin "2") (pinfunction "A_2") (pintype "passive"))
      (node (ref "D6") (pin "2") (pinfunction "A_2") (pintype "passive"))
      (node (ref "R9") (pin "1") (pinfunction "1_1") (pintype "passive"))
    )
    (net (code "33") (name "VDD") (class "Default")
      (node (ref "C27") (pin "2") (pinfunction "2_2") (pintype "passive"))
      (node (ref "C28") (pin "2") (pinfunction "2_2") (pintype "passive"))
      (node (ref "C29") (pin "2") (pinfunction "2_2") (pintype "passive"))
      (node (ref "R3") (pin "2") (pinfunction "2_2") (pintype "passive"))
      (node (ref "U5") (pin "3") (pinfunction "Output_3") (pintype "passive"))
    )
    (net (code "34") (name "VIN") (class "Default")
      (node (ref "C1") (pin "2") (pinfunction "A_2") (pintype "passive"))
      (node (ref "C2") (pin "2") (pinfunction "A_2") (pintype "passive"))
      (node (ref "C3") (pin "2") (pinfunction "A_2") (pintype "passive"))
      (node (ref "C4") (pin "2") (pinfunction "A_2") (pintype "passive"))
      (node (ref "C5") (pin "2") (pinfunction "A_2") (pintype "passive"))
      (node (ref "C6") (pin "2") (pinfunction "2_2") (pintype "passive"))
      (node (ref "C7") (pin "2") (pinfunction "2_2") (pintype "passive"))
      (node (ref "C8") (pin "2") (pinfunction "2_2") (pintype "passive"))
      (node (ref "D4") (pin "2") (pinfunction "A_2") (pintype "passive"))
      (node (ref "Q1") (pin "5") (pinfunction "DRAIN_5") (pintype "passive"))
      (node (ref "Q1") (pin "6") (pinfunction "DRAIN_6") (pintype "passive"))
      (node (ref "Q1") (pin "7") (pinfunction "DRAIN_7") (pintype "passive"))
      (node (ref "Q1") (pin "8") (pinfunction "DRAIN_8") (pintype "passive"))
      (node (ref "R10") (pin "2") (pinfunction "2_2") (pintype "passive"))
      (node (ref "R8") (pin "2") (pinfunction "2_2") (pintype "passive"))
      (node (ref "U3") (pin "3") (pinfunction "VISNS_3") (pintype "passive"))
    )
  )
)
